# new_controller.net
KiCad netlist of a schematic drawn in Altium Designer
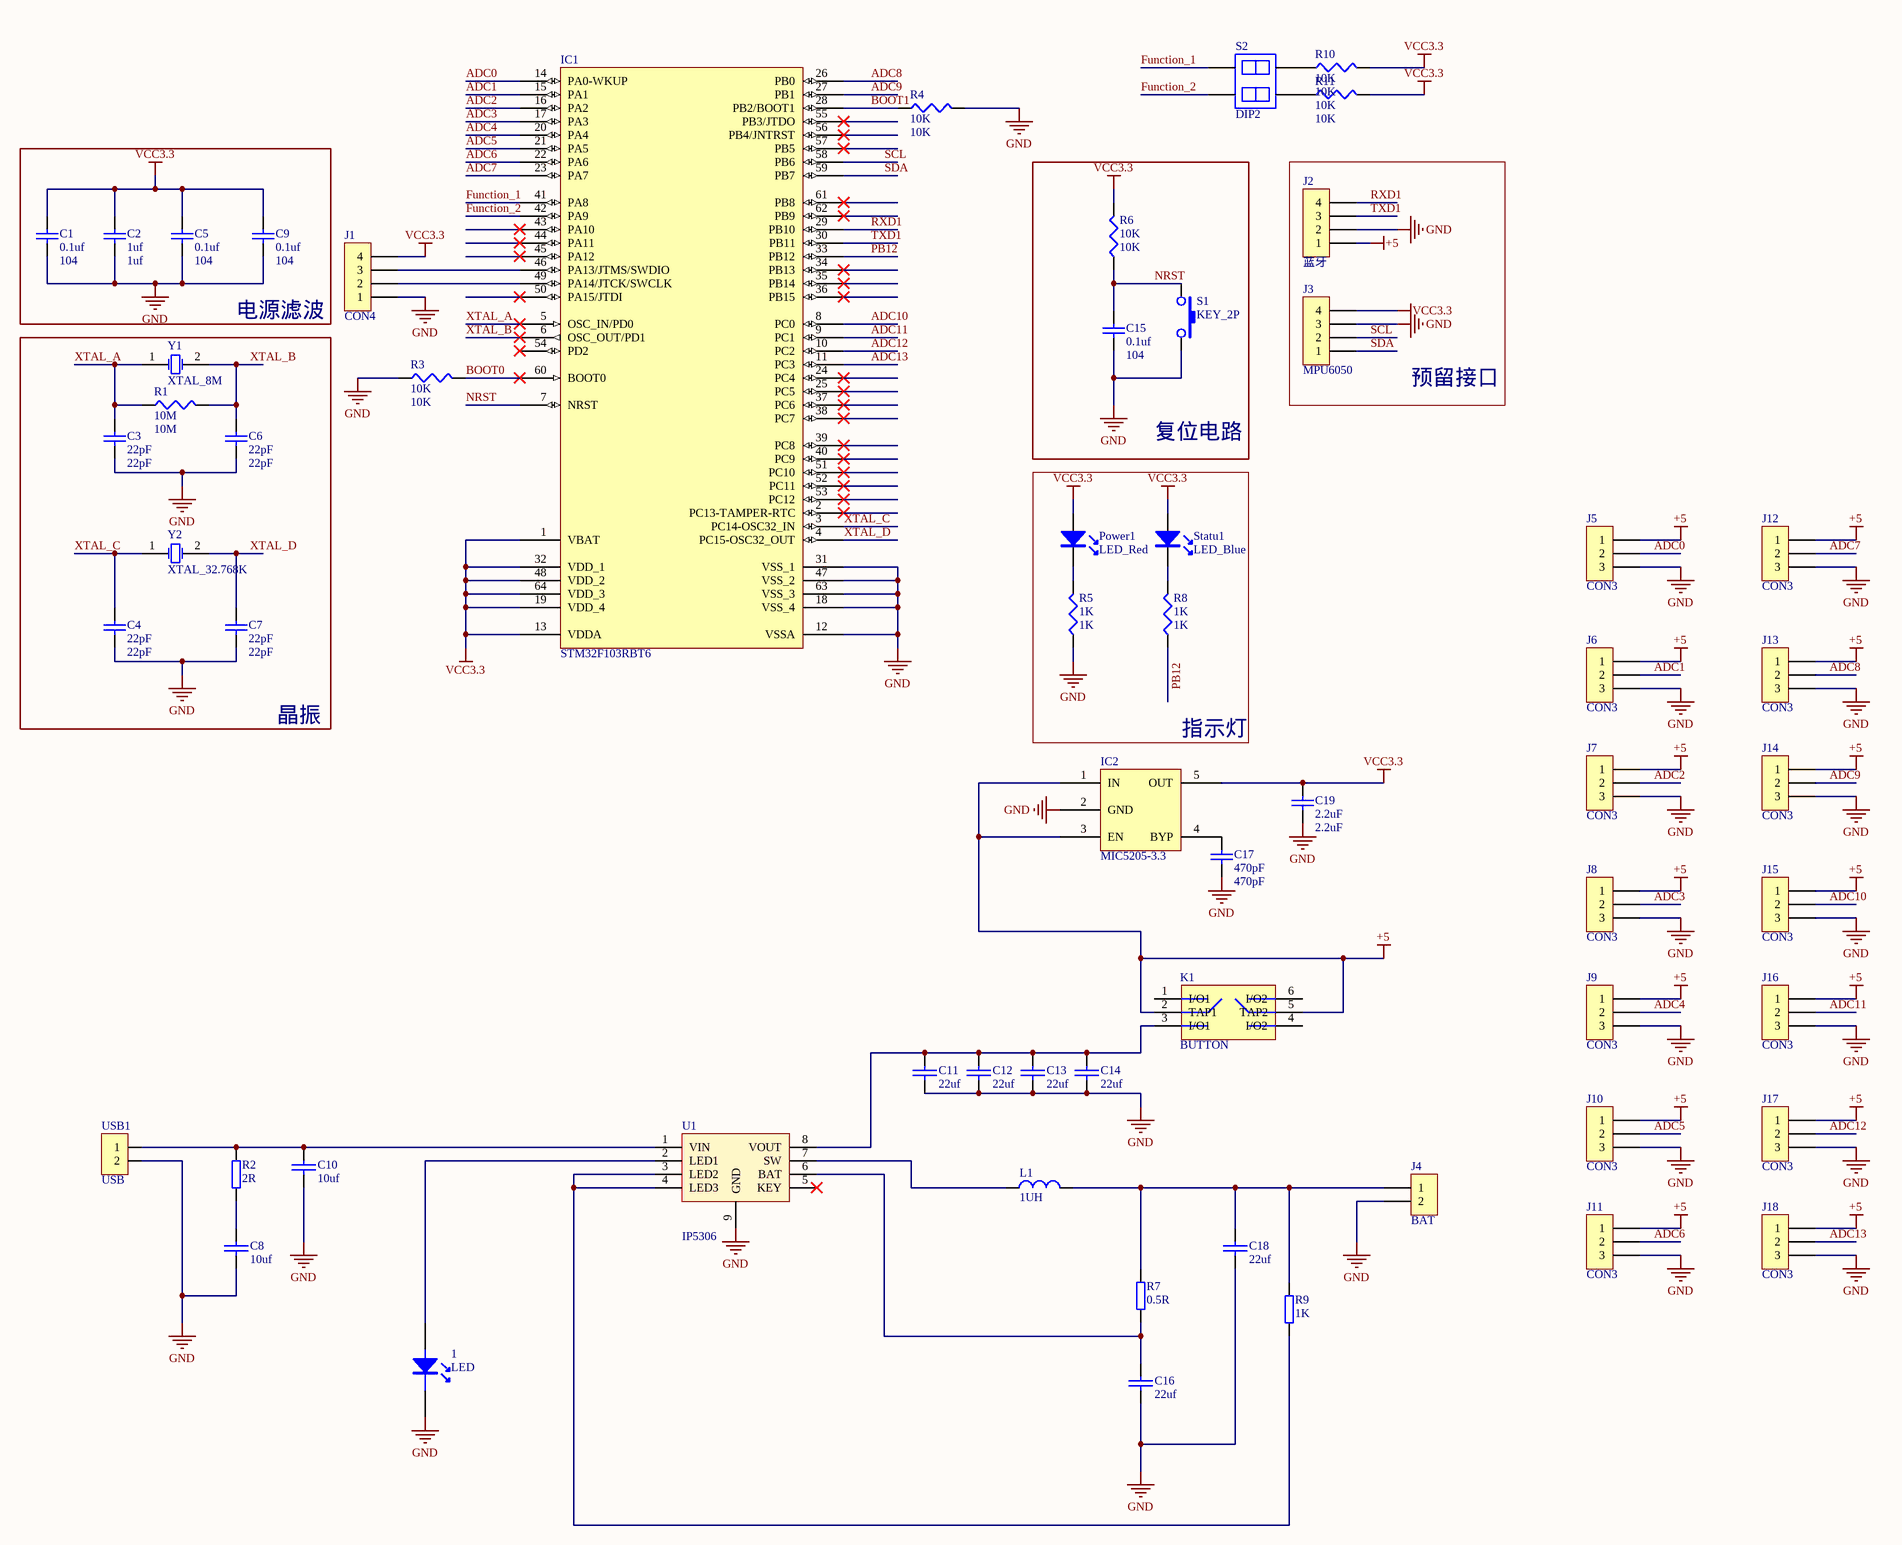
[diagram p0: new_controller.SchDoc]

(export (version "E")
  (design (tool "Eeschema 10.0.6"))
  (components
    (comp (ref "1") (value "LED") (footprint "6-0805_L") (libsource (lib "杂元件库") (part "LED")))
    (comp (ref "C1")
      (value "0.1uf")
      (footprint "6-0805_L")
      (description "Capacitor (Semiconductor SIM Model)")
      (fields (field (name "ALTIUM_VALUE") "104") (field (name "PUBLISHER") "Altium Limited"))
      (libsource (lib "Miscellaneous Devices") (part "Cap Semi"))
    )
    (comp (ref "C2")
      (value "1uf")
      (footprint "6-0805_L")
      (description "Capacitor (Semiconductor SIM Model)")
      (fields (field (name "ALTIUM_VALUE") "1uf") (field (name "PUBLISHER") "Altium Limited"))
      (libsource (lib "Miscellaneous Devices") (part "Cap Semi"))
    )
    (comp (ref "C3")
      (value "22pF")
      (footprint "6-0805_L")
      (description "Capacitor (Semiconductor SIM Model)")
      (fields (field (name "ALTIUM_VALUE") "22pF") (field (name "PUBLISHER") "Altium Limited"))
      (libsource (lib "Miscellaneous Devices") (part "Cap Semi"))
    )
    (comp (ref "C4")
      (value "22pF")
      (footprint "6-0805_L")
      (description "Capacitor (Semiconductor SIM Model)")
      (fields (field (name "ALTIUM_VALUE") "22pF") (field (name "PUBLISHER") "Altium Limited"))
      (libsource (lib "Miscellaneous Devices") (part "Cap Semi"))
    )
    (comp (ref "C5")
      (value "0.1uf")
      (footprint "6-0805_L")
      (description "Capacitor (Semiconductor SIM Model)")
      (fields (field (name "ALTIUM_VALUE") "104") (field (name "PUBLISHER") "Altium Limited"))
      (libsource (lib "Miscellaneous Devices") (part "Cap Semi"))
    )
    (comp (ref "C6")
      (value "22pF")
      (footprint "6-0805_L")
      (description "Capacitor (Semiconductor SIM Model)")
      (fields (field (name "ALTIUM_VALUE") "22pF") (field (name "PUBLISHER") "Altium Limited"))
      (libsource (lib "Miscellaneous Devices") (part "Cap Semi"))
    )
    (comp (ref "C7")
      (value "22pF")
      (footprint "6-0805_L")
      (description "Capacitor (Semiconductor SIM Model)")
      (fields (field (name "ALTIUM_VALUE") "22pF") (field (name "PUBLISHER") "Altium Limited"))
      (libsource (lib "Miscellaneous Devices") (part "Cap Semi"))
    )
    (comp (ref "C8")
      (value "10uf")
      (footprint "6-0805_L")
      (description "电容")
      (libsource (lib "Component") (part "CAP"))
    )
    (comp (ref "C9")
      (value "0.1uf")
      (footprint "6-0805_L")
      (description "Capacitor (Semiconductor SIM Model)")
      (fields (field (name "ALTIUM_VALUE") "104") (field (name "PUBLISHER") "Altium Limited"))
      (libsource (lib "Miscellaneous Devices") (part "Cap Semi"))
    )
    (comp (ref "C10")
      (value "10uf")
      (footprint "6-0805_L")
      (description "电容")
      (libsource (lib "Component") (part "CAP"))
    )
    (comp (ref "C11")
      (value "22uf")
      (footprint "6-0805_L")
      (description "电容")
      (libsource (lib "Component") (part "CAP"))
    )
    (comp (ref "C12")
      (value "22uf")
      (footprint "6-0805_L")
      (description "电容")
      (libsource (lib "Component") (part "CAP"))
    )
    (comp (ref "C13")
      (value "22uf")
      (footprint "6-0805_L")
      (description "电容")
      (libsource (lib "Component") (part "CAP"))
    )
    (comp (ref "C14")
      (value "22uf")
      (footprint "6-0805_L")
      (description "电容")
      (libsource (lib "Component") (part "CAP"))
    )
    (comp (ref "C15")
      (value "0.1uf")
      (footprint "6-0805_L")
      (description "Capacitor (Semiconductor SIM Model)")
      (fields (field (name "ALTIUM_VALUE") "104") (field (name "PUBLISHER") "Altium Limited"))
      (libsource (lib "Miscellaneous Devices") (part "Cap Semi"))
    )
    (comp (ref "C16")
      (value "22uf")
      (footprint "6-0805_L")
      (description "电容")
      (libsource (lib "Component") (part "CAP"))
    )
    (comp (ref "C17")
      (value "470pF")
      (footprint "6-0805_L")
      (description "Capacitor (Semiconductor SIM Model)")
      (fields (field (name "ALTIUM_VALUE") "470pF") (field (name "PUBLISHER") "Altium Limited"))
      (libsource (lib "Miscellaneous Devices") (part "Cap Semi"))
    )
    (comp (ref "C18")
      (value "22uf")
      (footprint "6-0805_L")
      (description "电容")
      (libsource (lib "Component") (part "CAP"))
    )
    (comp (ref "C19")
      (value "2.2uF")
      (footprint "6-0805_L")
      (description "Capacitor (Semiconductor SIM Model)")
      (fields (field (name "ALTIUM_VALUE") "2.2uF") (field (name "PUBLISHER") "Altium Limited"))
      (libsource (lib "Miscellaneous Devices") (part "Cap Semi"))
    )
    (comp (ref "IC1")
      (value "STM32F103RBT6")
      (footprint "LQFP64_N")
      (description "STM32 ARM-based 32-bit MCU with 128 Kbytes Flash, 64-pin LQFP, Industrial Temperature")
      (fields (field (name "PUBLISHER") "Altium Limited"))
      (libsource (lib "ST Microcontroller 32-Bit STM32") (part "STM32F103RBT6"))
    )
    (comp (ref "IC2")
      (value "MIC5205-3.3")
      (footprint "SOT-23-5")
      (description "稳压")
      (libsource (lib "Chip") (part "MIC5205-3.3"))
    )
    (comp (ref "J1")
      (value "CON4")
      (footprint "HDR1X4")
      (description "连接器")
      (libsource (lib "Connector") (part "CON4"))
    )
    (comp (ref "J2")
      (value "蓝牙")
      (footprint "HDR1X4")
      (description "Connector")
      (libsource (lib "杂元件库") (part "CON4"))
    )
    (comp (ref "J3")
      (value "MPU6050")
      (footprint "HDR1X4")
      (description "Connector")
      (libsource (lib "杂元件库") (part "CON4"))
    )
    (comp (ref "J4")
      (value "BAT")
      (footprint "接线座2P")
      (description "连接器")
      (libsource (lib "Connector") (part "CON2"))
    )
    (comp (ref "J5")
      (value "CON3")
      (footprint "XH2.54-3P")
      (description "连接器")
      (libsource (lib "Connector") (part "CON3"))
    )
    (comp (ref "J6")
      (value "CON3")
      (footprint "XH2.54-3P")
      (description "连接器")
      (libsource (lib "Connector") (part "CON3"))
    )
    (comp (ref "J7")
      (value "CON3")
      (footprint "XH2.54-3P")
      (description "连接器")
      (libsource (lib "Connector") (part "CON3"))
    )
    (comp (ref "J8")
      (value "CON3")
      (footprint "XH2.54-3P")
      (description "连接器")
      (libsource (lib "Connector") (part "CON3"))
    )
    (comp (ref "J9")
      (value "CON3")
      (footprint "XH2.54-3P")
      (description "连接器")
      (libsource (lib "Connector") (part "CON3"))
    )
    (comp (ref "J10")
      (value "CON3")
      (footprint "XH2.54-3P")
      (description "连接器")
      (libsource (lib "Connector") (part "CON3"))
    )
    (comp (ref "J11")
      (value "CON3")
      (footprint "XH2.54-3P")
      (description "连接器")
      (libsource (lib "Connector") (part "CON3"))
    )
    (comp (ref "J12")
      (value "CON3")
      (footprint "XH2.54-3P")
      (description "连接器")
      (libsource (lib "Connector") (part "CON3"))
    )
    (comp (ref "J13")
      (value "CON3")
      (footprint "XH2.54-3P")
      (description "连接器")
      (libsource (lib "Connector") (part "CON3"))
    )
    (comp (ref "J14")
      (value "CON3")
      (footprint "XH2.54-3P")
      (description "连接器")
      (libsource (lib "Connector") (part "CON3"))
    )
    (comp (ref "J15")
      (value "CON3")
      (footprint "XH2.54-3P")
      (description "连接器")
      (libsource (lib "Connector") (part "CON3"))
    )
    (comp (ref "J16")
      (value "CON3")
      (footprint "XH2.54-3P")
      (description "连接器")
      (libsource (lib "Connector") (part "CON3"))
    )
    (comp (ref "J17")
      (value "CON3")
      (footprint "XH2.54-3P")
      (description "连接器")
      (libsource (lib "Connector") (part "CON3"))
    )
    (comp (ref "J18")
      (value "CON3")
      (footprint "XH2.54-3P")
      (description "连接器")
      (libsource (lib "Connector") (part "CON3"))
    )
    (comp (ref "K1")
      (value "BUTTON")
      (footprint "My:switch")
      (description "自锁按键")
      (libsource (lib "Component") (part "BUTTON"))
    )
    (comp (ref "L1")
      (value "1UH")
      (footprint "0630电感")
      (description "电感")
      (libsource (lib "Component") (part "Inductor"))
    )
    (comp (ref "Power1")
      (value "LED_Red")
      (footprint "6-0805_M")
      (description "LED")
      (libsource (lib "Component") (part "LED"))
    )
    (comp (ref "R1")
      (value "10M")
      (footprint "6-0805_L")
      (description "Resistor")
      (fields (field (name "ALTIUM_VALUE") "10M") (field (name "PUBLISHER") "Altium Limited"))
      (libsource (lib "Miscellaneous Devices") (part "Res3"))
    )
    (comp (ref "R2")
      (value "2R")
      (footprint "6-0805_L")
      (description "电阻")
      (libsource (lib "Component") (part "RES"))
    )
    (comp (ref "R3")
      (value "10K")
      (footprint "6-0805_L")
      (description "Resistor")
      (fields (field (name "ALTIUM_VALUE") "10K") (field (name "PUBLISHER") "Altium Limited"))
      (libsource (lib "Miscellaneous Devices") (part "Res3"))
    )
    (comp (ref "R4")
      (value "10K")
      (footprint "6-0805_L")
      (description "Resistor")
      (fields (field (name "ALTIUM_VALUE") "10K") (field (name "PUBLISHER") "Altium Limited"))
      (libsource (lib "Miscellaneous Devices") (part "Res3"))
    )
    (comp (ref "R5")
      (value "1K")
      (footprint "6-0805_L")
      (description "Resistor")
      (fields (field (name "ALTIUM_VALUE") "1K") (field (name "PUBLISHER") "Altium Limited"))
      (libsource (lib "Miscellaneous Devices") (part "Res3"))
    )
    (comp (ref "R6")
      (value "10K")
      (footprint "6-0805_L")
      (description "Resistor")
      (fields (field (name "ALTIUM_VALUE") "10K") (field (name "PUBLISHER") "Altium Limited"))
      (libsource (lib "Miscellaneous Devices") (part "Res3"))
    )
    (comp (ref "R7")
      (value "0.5R")
      (footprint "6-0805_L")
      (description "电阻")
      (libsource (lib "Component") (part "RES"))
    )
    (comp (ref "R8")
      (value "1K")
      (footprint "6-0805_L")
      (description "Resistor")
      (fields (field (name "ALTIUM_VALUE") "1K") (field (name "PUBLISHER") "Altium Limited"))
      (libsource (lib "Miscellaneous Devices") (part "Res3"))
    )
    (comp (ref "R9")
      (value "1K")
      (footprint "6-0805_L")
      (description "电阻")
      (libsource (lib "Component") (part "RES"))
    )
    (comp (ref "R10")
      (value "10K")
      (footprint "6-0805_L")
      (description "Resistor")
      (fields (field (name "ALTIUM_VALUE") "10K") (field (name "PUBLISHER") "Altium Limited"))
      (libsource (lib "Miscellaneous Devices") (part "Res3"))
    )
    (comp (ref "R11")
      (value "10K")
      (footprint "6-0805_L")
      (description "Resistor")
      (fields (field (name "ALTIUM_VALUE") "10K") (field (name "PUBLISHER") "Altium Limited"))
      (libsource (lib "Miscellaneous Devices") (part "Res3"))
    )
    (comp (ref "S1")
      (value "KEY_2P")
      (footprint "My:button")
      (description "轻触按键2P")
      (libsource (lib "Component") (part "KEY_2P"))
    )
    (comp (ref "S2") (value "DIP2") (footprint "DIP2") (libsource (lib "My") (part "拨码开关2DIP")))
    (comp (ref "Statu1")
      (value "LED_Blue")
      (footprint "6-0805_M")
      (description "LED")
      (libsource (lib "Component") (part "LED"))
    )
    (comp (ref "U1") (value "IP5306") (footprint "ESOP8") (libsource (lib "My") (part "IP5306")))
    (comp (ref "USB1")
      (value "USB")
      (footprint "Type-C")
      (description "Conjunctor")
      (libsource (lib "zj") (part "CON2"))
    )
    (comp (ref "Y1")
      (value "XTAL_8M")
      (footprint "xtal")
      (description "Crystal Oscillator")
      (fields (field (name "PUBLISHER") "Altium Limited"))
      (libsource (lib "Miscellaneous Devices") (part "XTAL"))
    )
    (comp (ref "Y2")
      (value "XTAL_32.768K")
      (footprint "R38")
      (description "Crystal Oscillator")
      (fields (field (name "PUBLISHER") "Altium Limited"))
      (libsource (lib "Miscellaneous Devices") (part "XTAL"))
    )
  )
  (nets
    (net (code "1") (name "+5") (class "Default")
      (node (ref "IC2") (pin "1") (pinfunction "IN_1") (pintype "passive"))
      (node (ref "IC2") (pin "3") (pinfunction "EN_3") (pintype "passive"))
      (node (ref "J10") (pin "1") (pinfunction "1_1") (pintype "passive"))
      (node (ref "J11") (pin "1") (pinfunction "1_1") (pintype "passive"))
      (node (ref "J12") (pin "1") (pinfunction "1_1") (pintype "passive"))
      (node (ref "J13") (pin "1") (pinfunction "1_1") (pintype "passive"))
      (node (ref "J14") (pin "1") (pinfunction "1_1") (pintype "passive"))
      (node (ref "J15") (pin "1") (pinfunction "1_1") (pintype "passive"))
      (node (ref "J16") (pin "1") (pinfunction "1_1") (pintype "passive"))
      (node (ref "J17") (pin "1") (pinfunction "1_1") (pintype "passive"))
      (node (ref "J18") (pin "1") (pinfunction "1_1") (pintype "passive"))
      (node (ref "J2") (pin "1") (pinfunction "1_1") (pintype "passive"))
      (node (ref "J5") (pin "1") (pinfunction "1_1") (pintype "passive"))
      (node (ref "J6") (pin "1") (pinfunction "1_1") (pintype "passive"))
      (node (ref "J7") (pin "1") (pinfunction "1_1") (pintype "passive"))
      (node (ref "J8") (pin "1") (pinfunction "1_1") (pintype "passive"))
      (node (ref "J9") (pin "1") (pinfunction "1_1") (pintype "passive"))
      (node (ref "K1") (pin "2") (pinfunction "TAP1_2") (pintype "passive"))
      (node (ref "K1") (pin "5") (pinfunction "TAP2_5") (pintype "passive"))
    )
    (net (code "2") (name "/ADC0") (class "Default")
      (node (ref "IC1") (pin "14") (pinfunction "PA0-WKUP_14") (pintype "bidirectional"))
      (node (ref "J5") (pin "2") (pinfunction "2_2") (pintype "passive"))
    )
    (net (code "3") (name "/ADC1") (class "Default")
      (node (ref "IC1") (pin "15") (pinfunction "PA1_15") (pintype "bidirectional"))
      (node (ref "J6") (pin "2") (pinfunction "2_2") (pintype "passive"))
    )
    (net (code "4") (name "/ADC2") (class "Default")
      (node (ref "IC1") (pin "16") (pinfunction "PA2_16") (pintype "bidirectional"))
      (node (ref "J7") (pin "2") (pinfunction "2_2") (pintype "passive"))
    )
    (net (code "5") (name "/ADC3") (class "Default")
      (node (ref "IC1") (pin "17") (pinfunction "PA3_17") (pintype "bidirectional"))
      (node (ref "J8") (pin "2") (pinfunction "2_2") (pintype "passive"))
    )
    (net (code "6") (name "/ADC4") (class "Default")
      (node (ref "IC1") (pin "20") (pinfunction "PA4_20") (pintype "bidirectional"))
      (node (ref "J9") (pin "2") (pinfunction "2_2") (pintype "passive"))
    )
    (net (code "7") (name "/ADC5") (class "Default")
      (node (ref "IC1") (pin "21") (pinfunction "PA5_21") (pintype "bidirectional"))
      (node (ref "J10") (pin "2") (pinfunction "2_2") (pintype "passive"))
    )
    (net (code "8") (name "/ADC6") (class "Default")
      (node (ref "IC1") (pin "22") (pinfunction "PA6_22") (pintype "bidirectional"))
      (node (ref "J11") (pin "2") (pinfunction "2_2") (pintype "passive"))
    )
    (net (code "9") (name "/ADC7") (class "Default")
      (node (ref "IC1") (pin "23") (pinfunction "PA7_23") (pintype "bidirectional"))
      (node (ref "J12") (pin "2") (pinfunction "2_2") (pintype "passive"))
    )
    (net (code "10") (name "/ADC8") (class "Default")
      (node (ref "IC1") (pin "26") (pinfunction "PB0_26") (pintype "bidirectional"))
      (node (ref "J13") (pin "2") (pinfunction "2_2") (pintype "passive"))
    )
    (net (code "11") (name "/ADC9") (class "Default")
      (node (ref "IC1") (pin "27") (pinfunction "PB1_27") (pintype "bidirectional"))
      (node (ref "J14") (pin "2") (pinfunction "2_2") (pintype "passive"))
    )
    (net (code "12") (name "/ADC10") (class "Default")
      (node (ref "IC1") (pin "8") (pinfunction "PC0_8") (pintype "bidirectional"))
      (node (ref "J15") (pin "2") (pinfunction "2_2") (pintype "passive"))
    )
    (net (code "13") (name "/ADC11") (class "Default")
      (node (ref "IC1") (pin "9") (pinfunction "PC1_9") (pintype "bidirectional"))
      (node (ref "J16") (pin "2") (pinfunction "2_2") (pintype "passive"))
    )
    (net (code "14") (name "/ADC12") (class "Default")
      (node (ref "IC1") (pin "10") (pinfunction "PC2_10") (pintype "bidirectional"))
      (node (ref "J17") (pin "2") (pinfunction "2_2") (pintype "passive"))
    )
    (net (code "15") (name "/ADC13") (class "Default")
      (node (ref "IC1") (pin "11") (pinfunction "PC3_11") (pintype "bidirectional"))
      (node (ref "J18") (pin "2") (pinfunction "2_2") (pintype "passive"))
    )
    (net (code "16") (name "/BOOT0") (class "Default")
      (node (ref "IC1") (pin "60") (pinfunction "BOOT0_60") (pintype "input"))
      (node (ref "R3") (pin "2") (pinfunction "2_2") (pintype "passive"))
    )
    (net (code "17") (name "/BOOT1") (class "Default")
      (node (ref "IC1") (pin "28") (pinfunction "PB2/BOOT1_28") (pintype "bidirectional"))
      (node (ref "R4") (pin "1") (pinfunction "1_1") (pintype "passive"))
    )
    (net (code "18") (name "/Function_1") (class "Default")
      (node (ref "IC1") (pin "41") (pinfunction "PA8_41") (pintype "bidirectional"))
      (node (ref "S2") (pin "1") (pinfunction "1_1") (pintype "passive"))
    )
    (net (code "19") (name "/Function_2") (class "Default")
      (node (ref "IC1") (pin "42") (pinfunction "PA9_42") (pintype "bidirectional"))
      (node (ref "S2") (pin "2") (pinfunction "2_2") (pintype "passive"))
    )
    (net (code "20") (name "/NRST") (class "Default")
      (node (ref "C15") (pin "2") (pinfunction "2_2") (pintype "passive"))
      (node (ref "IC1") (pin "7") (pinfunction "NRST_7") (pintype "bidirectional"))
      (node (ref "R6") (pin "1") (pinfunction "1_1") (pintype "passive"))
      (node (ref "S1") (pin "1") (pinfunction "1_1") (pintype "passive"))
    )
    (net (code "21") (name "/PB12") (class "Default")
      (node (ref "IC1") (pin "33") (pinfunction "PB12_33") (pintype "bidirectional"))
      (node (ref "R8") (pin "1") (pinfunction "1_1") (pintype "passive"))
    )
    (net (code "22") (name "/RXD1") (class "Default")
      (node (ref "IC1") (pin "29") (pinfunction "PB10_29") (pintype "bidirectional"))
      (node (ref "J2") (pin "4") (pinfunction "4_4") (pintype "passive"))
    )
    (net (code "23") (name "/SCL") (class "Default")
      (node (ref "IC1") (pin "58") (pinfunction "PB6_58") (pintype "bidirectional"))
      (node (ref "J3") (pin "2") (pinfunction "2_2") (pintype "passive"))
    )
    (net (code "24") (name "/SDA") (class "Default")
      (node (ref "IC1") (pin "59") (pinfunction "PB7_59") (pintype "bidirectional"))
      (node (ref "J3") (pin "1") (pinfunction "1_1") (pintype "passive"))
    )
    (net (code "25") (name "/TXD1") (class "Default")
      (node (ref "IC1") (pin "30") (pinfunction "PB11_30") (pintype "bidirectional"))
      (node (ref "J2") (pin "3") (pinfunction "3_3") (pintype "passive"))
    )
    (net (code "26") (name "/XTAL_A") (class "Default")
      (node (ref "C3") (pin "2") (pinfunction "2_2") (pintype "passive"))
      (node (ref "IC1") (pin "5") (pinfunction "OSC_IN/PD0_5") (pintype "input"))
      (node (ref "R1") (pin "1") (pinfunction "1_1") (pintype "passive"))
      (node (ref "Y1") (pin "1") (pinfunction "OSC1_1") (pintype "passive"))
    )
    (net (code "27") (name "/XTAL_B") (class "Default")
      (node (ref "C6") (pin "2") (pinfunction "2_2") (pintype "passive"))
      (node (ref "IC1") (pin "6") (pinfunction "OSC_OUT/PD1_6") (pintype "output"))
      (node (ref "R1") (pin "2") (pinfunction "2_2") (pintype "passive"))
      (node (ref "Y1") (pin "2") (pinfunction "OSC2_2") (pintype "passive"))
    )
    (net (code "28") (name "/XTAL_C") (class "Default")
      (node (ref "C4") (pin "2") (pinfunction "2_2") (pintype "passive"))
      (node (ref "IC1") (pin "3") (pinfunction "PC14-OSC32_IN_3") (pintype "bidirectional"))
      (node (ref "Y2") (pin "1") (pinfunction "OSC1_1") (pintype "passive"))
    )
    (net (code "29") (name "/XTAL_D") (class "Default")
      (node (ref "C7") (pin "2") (pinfunction "2_2") (pintype "passive"))
      (node (ref "IC1") (pin "4") (pinfunction "PC15-OSC32_OUT_4") (pintype "bidirectional"))
      (node (ref "Y2") (pin "2") (pinfunction "OSC2_2") (pintype "passive"))
    )
    (net (code "30") (name "GND") (class "Default")
      (node (ref "1") (pin "K") (pinfunction "2_K") (pintype "passive"))
      (node (ref "C1") (pin "1") (pinfunction "1_1") (pintype "passive"))
      (node (ref "C10") (pin "2") (pinfunction "2_2") (pintype "passive"))
      (node (ref "C11") (pin "2") (pinfunction "2_2") (pintype "passive"))
      (node (ref "C12") (pin "2") (pinfunction "2_2") (pintype "passive"))
      (node (ref "C13") (pin "2") (pinfunction "2_2") (pintype "passive"))
      (node (ref "C14") (pin "2") (pinfunction "2_2") (pintype "passive"))
      (node (ref "C15") (pin "1") (pinfunction "1_1") (pintype "passive"))
      (node (ref "C16") (pin "2") (pinfunction "2_2") (pintype "passive"))
      (node (ref "C17") (pin "1") (pinfunction "1_1") (pintype "passive"))
      (node (ref "C18") (pin "2") (pinfunction "2_2") (pintype "passive"))
      (node (ref "C19") (pin "1") (pinfunction "1_1") (pintype "passive"))
      (node (ref "C2") (pin "1") (pinfunction "1_1") (pintype "passive"))
      (node (ref "C3") (pin "1") (pinfunction "1_1") (pintype "passive"))
      (node (ref "C4") (pin "1") (pinfunction "1_1") (pintype "passive"))
      (node (ref "C5") (pin "1") (pinfunction "1_1") (pintype "passive"))
      (node (ref "C6") (pin "1") (pinfunction "1_1") (pintype "passive"))
      (node (ref "C7") (pin "1") (pinfunction "1_1") (pintype "passive"))
      (node (ref "C8") (pin "2") (pinfunction "2_2") (pintype "passive"))
      (node (ref "C9") (pin "1") (pinfunction "1_1") (pintype "passive"))
      (node (ref "IC1") (pin "12") (pinfunction "VSSA_12") (pintype "power_in"))
      (node (ref "IC1") (pin "18") (pinfunction "VSS_4_18") (pintype "power_in"))
      (node (ref "IC1") (pin "31") (pinfunction "VSS_1_31") (pintype "power_in"))
      (node (ref "IC1") (pin "47") (pinfunction "VSS_2_47") (pintype "power_in"))
      (node (ref "IC1") (pin "63") (pinfunction "VSS_3_63") (pintype "power_in"))
      (node (ref "IC2") (pin "2") (pinfunction "GND_2") (pintype "passive"))
      (node (ref "J1") (pin "1") (pinfunction "1_1") (pintype "passive"))
      (node (ref "J10") (pin "3") (pinfunction "3_3") (pintype "passive"))
      (node (ref "J11") (pin "3") (pinfunction "3_3") (pintype "passive"))
      (node (ref "J12") (pin "3") (pinfunction "3_3") (pintype "passive"))
      (node (ref "J13") (pin "3") (pinfunction "3_3") (pintype "passive"))
      (node (ref "J14") (pin "3") (pinfunction "3_3") (pintype "passive"))
      (node (ref "J15") (pin "3") (pinfunction "3_3") (pintype "passive"))
      (node (ref "J16") (pin "3") (pinfunction "3_3") (pintype "passive"))
      (node (ref "J17") (pin "3") (pinfunction "3_3") (pintype "passive"))
      (node (ref "J18") (pin "3") (pinfunction "3_3") (pintype "passive"))
      (node (ref "J2") (pin "2") (pinfunction "2_2") (pintype "passive"))
      (node (ref "J3") (pin "3") (pinfunction "3_3") (pintype "passive"))
      (node (ref "J4") (pin "2") (pinfunction "2_2") (pintype "passive"))
      (node (ref "J5") (pin "3") (pinfunction "3_3") (pintype "passive"))
      (node (ref "J6") (pin "3") (pinfunction "3_3") (pintype "passive"))
      (node (ref "J7") (pin "3") (pinfunction "3_3") (pintype "passive"))
      (node (ref "J8") (pin "3") (pinfunction "3_3") (pintype "passive"))
      (node (ref "J9") (pin "3") (pinfunction "3_3") (pintype "passive"))
      (node (ref "R3") (pin "1") (pinfunction "1_1") (pintype "passive"))
      (node (ref "R4") (pin "2") (pinfunction "2_2") (pintype "passive"))
      (node (ref "R5") (pin "1") (pinfunction "1_1") (pintype "passive"))
      (node (ref "S1") (pin "2") (pinfunction "2_2") (pintype "passive"))
      (node (ref "U1") (pin "9") (pinfunction "GND_9") (pintype "passive"))
      (node (ref "USB1") (pin "2") (pinfunction "2_2") (pintype "passive"))
    )
    (net (code "31") (name "Net-(1-1)") (class "Default")
      (node (ref "1") (pin "A") (pinfunction "1_A") (pintype "passive"))
      (node (ref "U1") (pin "2") (pinfunction "LED1_2") (pintype "passive"))
    )
    (net (code "32") (name "Net-(C8-Pad1)") (class "Default")
      (node (ref "C8") (pin "1") (pinfunction "1_1") (pintype "passive"))
      (node (ref "R2") (pin "1") (pinfunction "1_1") (pintype "passive"))
    )
    (net (code "33") (name "Net-(C18-Pad1)") (class "Default")
      (node (ref "C18") (pin "1") (pinfunction "1_1") (pintype "passive"))
      (node (ref "J4") (pin "1") (pinfunction "1_1") (pintype "passive"))
      (node (ref "L1") (pin "2") (pinfunction "2_2") (pintype "passive"))
      (node (ref "R7") (pin "1") (pinfunction "1_1") (pintype "passive"))
      (node (ref "R9") (pin "1") (pinfunction "1_1") (pintype "passive"))
    )
    (net (code "34") (name "Net-(IC1-PA13{slash}JTMS{slash}SWDIO)") (class "Default")
      (node (ref "IC1") (pin "46") (pinfunction "PA13/JTMS/SWDIO_46") (pintype "bidirectional"))
      (node (ref "J1") (pin "3") (pinfunction "3_3") (pintype "passive"))
    )
    (net (code "35") (name "Net-(IC1-PA14{slash}JTCK{slash}SWCLK)") (class "Default")
      (node (ref "IC1") (pin "49") (pinfunction "PA14/JTCK/SWCLK_49") (pintype "bidirectional"))
      (node (ref "J1") (pin "2") (pinfunction "2_2") (pintype "passive"))
    )
    (net (code "36") (name "Net-(IC2-BYP)") (class "Default")
      (node (ref "C17") (pin "2") (pinfunction "2_2") (pintype "passive"))
      (node (ref "IC2") (pin "4") (pinfunction "BYP_4") (pintype "passive"))
    )
    (net (code "37") (name "Net-(Power1-Pad2)") (class "Default")
      (node (ref "Power1") (pin "2") (pinfunction "2_2") (pintype "passive"))
      (node (ref "R5") (pin "2") (pinfunction "2_2") (pintype "passive"))
    )
    (net (code "38") (name "Net-(R8-Pad2)") (class "Default")
      (node (ref "R8") (pin "2") (pinfunction "2_2") (pintype "passive"))
      (node (ref "Statu1") (pin "2") (pinfunction "2_2") (pintype "passive"))
    )
    (net (code "39") (name "Net-(R10-Pad1)") (class "Default")
      (node (ref "R10") (pin "1") (pinfunction "1_1") (pintype "passive"))
      (node (ref "S2") (pin "3") (pinfunction "3_3") (pintype "passive"))
    )
    (net (code "40") (name "Net-(R11-Pad1)") (class "Default")
      (node (ref "R11") (pin "1") (pinfunction "1_1") (pintype "passive"))
      (node (ref "S2") (pin "4") (pinfunction "4_4") (pintype "passive"))
    )
    (net (code "41") (name "Net-(U1-BAT)") (class "Default")
      (node (ref "C16") (pin "1") (pinfunction "1_1") (pintype "passive"))
      (node (ref "R7") (pin "2") (pinfunction "2_2") (pintype "passive"))
      (node (ref "U1") (pin "6") (pinfunction "BAT_6") (pintype "passive"))
    )
    (net (code "42") (name "Net-(U1-LED2)") (class "Default")
      (node (ref "R9") (pin "2") (pinfunction "2_2") (pintype "passive"))
      (node (ref "U1") (pin "3") (pinfunction "LED2_3") (pintype "passive"))
      (node (ref "U1") (pin "4") (pinfunction "LED3_4") (pintype "passive"))
    )
    (net (code "43") (name "Net-(U1-SW)") (class "Default")
      (node (ref "L1") (pin "1") (pinfunction "1_1") (pintype "passive"))
      (node (ref "U1") (pin "7") (pinfunction "SW_7") (pintype "passive"))
    )
    (net (code "44") (name "Net-(U1-VIN)") (class "Default")
      (node (ref "C10") (pin "1") (pinfunction "1_1") (pintype "passive"))
      (node (ref "R2") (pin "2") (pinfunction "2_2") (pintype "passive"))
      (node (ref "U1") (pin "1") (pinfunction "VIN_1") (pintype "passive"))
      (node (ref "USB1") (pin "1") (pinfunction "1_1") (pintype "passive"))
    )
    (net (code "45") (name "Net-(U1-VOUT)") (class "Default")
      (node (ref "C11") (pin "1") (pinfunction "1_1") (pintype "passive"))
      (node (ref "C12") (pin "1") (pinfunction "1_1") (pintype "passive"))
      (node (ref "C13") (pin "1") (pinfunction "1_1") (pintype "passive"))
      (node (ref "C14") (pin "1") (pinfunction "1_1") (pintype "passive"))
      (node (ref "K1") (pin "3") (pinfunction "I/O1_3") (pintype "passive"))
      (node (ref "U1") (pin "8") (pinfunction "VOUT_8") (pintype "passive"))
    )
    (net (code "46") (name "VCC3.3") (class "Default")
      (node (ref "C1") (pin "2") (pinfunction "2_2") (pintype "passive"))
      (node (ref "C19") (pin "2") (pinfunction "2_2") (pintype "passive"))
      (node (ref "C2") (pin "2") (pinfunction "2_2") (pintype "passive"))
      (node (ref "C5") (pin "2") (pinfunction "2_2") (pintype "passive"))
      (node (ref "C9") (pin "2") (pinfunction "2_2") (pintype "passive"))
      (node (ref "IC1") (pin "1") (pinfunction "VBAT_1") (pintype "power_in"))
      (node (ref "IC1") (pin "13") (pinfunction "VDDA_13") (pintype "power_in"))
      (node (ref "IC1") (pin "19") (pinfunction "VDD_4_19") (pintype "power_in"))
      (node (ref "IC1") (pin "32") (pinfunction "VDD_1_32") (pintype "power_in"))
      (node (ref "IC1") (pin "48") (pinfunction "VDD_2_48") (pintype "power_in"))
      (node (ref "IC1") (pin "64") (pinfunction "VDD_3_64") (pintype "power_in"))
      (node (ref "IC2") (pin "5") (pinfunction "OUT_5") (pintype "passive"))
      (node (ref "J1") (pin "4") (pinfunction "4_4") (pintype "passive"))
      (node (ref "J3") (pin "4") (pinfunction "4_4") (pintype "passive"))
      (node (ref "Power1") (pin "1") (pinfunction "1_1") (pintype "passive"))
      (node (ref "R10") (pin "2") (pinfunction "2_2") (pintype "passive"))
      (node (ref "R11") (pin "2") (pinfunction "2_2") (pintype "passive"))
      (node (ref "R6") (pin "2") (pinfunction "2_2") (pintype "passive"))
      (node (ref "Statu1") (pin "1") (pinfunction "1_1") (pintype "passive"))
    )
    (net (code "47") (name "unconnected-(IC1-PA10-Pad43)") (class "Default")
      (node (ref "IC1") (pin "43") (pinfunction "PA10_43") (pintype "bidirectional+no_connect"))
    )
    (net (code "48") (name "unconnected-(IC1-PA11-Pad44)") (class "Default")
      (node (ref "IC1") (pin "44") (pinfunction "PA11_44") (pintype "bidirectional+no_connect"))
    )
    (net (code "49") (name "unconnected-(IC1-PA12-Pad45)") (class "Default")
      (node (ref "IC1") (pin "45") (pinfunction "PA12_45") (pintype "bidirectional+no_connect"))
    )
    (net (code "50") (name "unconnected-(IC1-PA15{slash}JTDI-Pad50)") (class "Default")
      (node (ref "IC1") (pin "50") (pinfunction "PA15/JTDI_50") (pintype "bidirectional+no_connect"))
    )
    (net (code "51") (name "unconnected-(IC1-PB3{slash}JTDO-Pad55)") (class "Default")
      (node (ref "IC1") (pin "55") (pinfunction "PB3/JTDO_55") (pintype "bidirectional+no_connect"))
    )
    (net (code "52") (name "unconnected-(IC1-PB4{slash}JNTRST-Pad56)") (class "Default")
      (node (ref "IC1") (pin "56") (pinfunction "PB4/JNTRST_56") (pintype "bidirectional+no_connect"))
    )
    (net (code "53") (name "unconnected-(IC1-PB5-Pad57)") (class "Default")
      (node (ref "IC1") (pin "57") (pinfunction "PB5_57") (pintype "bidirectional+no_connect"))
    )
    (net (code "54") (name "unconnected-(IC1-PB8-Pad61)") (class "Default")
      (node (ref "IC1") (pin "61") (pinfunction "PB8_61") (pintype "bidirectional+no_connect"))
    )
    (net (code "55") (name "unconnected-(IC1-PB9-Pad62)") (class "Default")
      (node (ref "IC1") (pin "62") (pinfunction "PB9_62") (pintype "bidirectional+no_connect"))
    )
    (net (code "56") (name "unconnected-(IC1-PB13-Pad34)") (class "Default")
      (node (ref "IC1") (pin "34") (pinfunction "PB13_34") (pintype "bidirectional+no_connect"))
    )
    (net (code "57") (name "unconnected-(IC1-PB14-Pad35)") (class "Default")
      (node (ref "IC1") (pin "35") (pinfunction "PB14_35") (pintype "bidirectional+no_connect"))
    )
    (net (code "58") (name "unconnected-(IC1-PB15-Pad36)") (class "Default")
      (node (ref "IC1") (pin "36") (pinfunction "PB15_36") (pintype "bidirectional+no_connect"))
    )
    (net (code "59") (name "unconnected-(IC1-PC4-Pad24)") (class "Default")
      (node (ref "IC1") (pin "24") (pinfunction "PC4_24") (pintype "bidirectional+no_connect"))
    )
    (net (code "60") (name "unconnected-(IC1-PC5-Pad25)") (class "Default")
      (node (ref "IC1") (pin "25") (pinfunction "PC5_25") (pintype "bidirectional+no_connect"))
    )
    (net (code "61") (name "unconnected-(IC1-PC6-Pad37)") (class "Default")
      (node (ref "IC1") (pin "37") (pinfunction "PC6_37") (pintype "bidirectional+no_connect"))
    )
    (net (code "62") (name "unconnected-(IC1-PC7-Pad38)") (class "Default")
      (node (ref "IC1") (pin "38") (pinfunction "PC7_38") (pintype "bidirectional+no_connect"))
    )
    (net (code "63") (name "unconnected-(IC1-PC8-Pad39)") (class "Default")
      (node (ref "IC1") (pin "39") (pinfunction "PC8_39") (pintype "bidirectional+no_connect"))
    )
    (net (code "64") (name "unconnected-(IC1-PC9-Pad40)") (class "Default")
      (node (ref "IC1") (pin "40") (pinfunction "PC9_40") (pintype "bidirectional+no_connect"))
    )
    (net (code "65") (name "unconnected-(IC1-PC10-Pad51)") (class "Default")
      (node (ref "IC1") (pin "51") (pinfunction "PC10_51") (pintype "bidirectional+no_connect"))
    )
    (net (code "66") (name "unconnected-(IC1-PC11-Pad52)") (class "Default")
      (node (ref "IC1") (pin "52") (pinfunction "PC11_52") (pintype "bidirectional+no_connect"))
    )
    (net (code "67") (name "unconnected-(IC1-PC12-Pad53)") (class "Default")
      (node (ref "IC1") (pin "53") (pinfunction "PC12_53") (pintype "bidirectional+no_connect"))
    )
    (net (code "68") (name "unconnected-(IC1-PC13-TAMPER-RTC-Pad2)") (class "Default")
      (node (ref "IC1") (pin "2") (pinfunction "PC13-TAMPER-RTC_2") (pintype "bidirectional+no_connect"))
    )
    (net (code "69") (name "unconnected-(IC1-PD2-Pad54)") (class "Default")
      (node (ref "IC1") (pin "54") (pinfunction "PD2_54") (pintype "bidirectional+no_connect"))
    )
    (net (code "70") (name "unconnected-(K1-I{slash}O1-Pad1)") (class "Default")
      (node (ref "K1") (pin "1") (pinfunction "I/O1_1") (pintype "passive"))
    )
    (net (code "71") (name "unconnected-(K1-I{slash}O2-Pad4)") (class "Default")
      (node (ref "K1") (pin "4") (pinfunction "I/O2_4") (pintype "passive"))
    )
    (net (code "72") (name "unconnected-(K1-I{slash}O2-Pad6)") (class "Default")
      (node (ref "K1") (pin "6") (pinfunction "I/O2_6") (pintype "passive"))
    )
    (net (code "73") (name "unconnected-(U1-KEY-Pad5)") (class "Default")
      (node (ref "U1") (pin "5") (pinfunction "KEY_5") (pintype "passive+no_connect"))
    )
  )
)
